# alarm-interface.net
KiCad netlist of a schematic drawn in Altium Designer
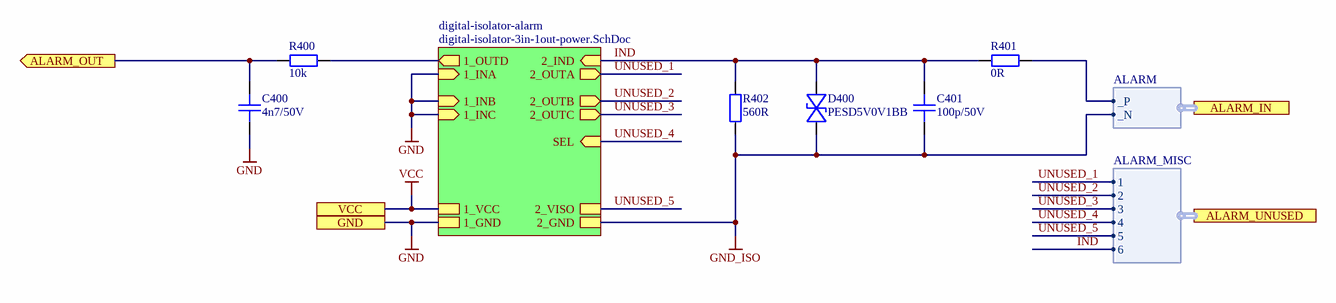
[diagram p0: alarm-interface.SchDoc]

(export (version "E")
  (design (tool "Eeschema 10.0.6"))
  (components
    (comp (ref "C400")
      (value "4n7/50V")
      (footprint "CAPC1608X08N")
      (description "MLCC")
      (fields (field (name "PART NUMBER") "gen_C_ceramic_4n7_50V_X7R_0603"))
      (libsource (lib "OE750") (part "C"))
    )
    (comp (ref "C401")
      (value "100p/50V")
      (footprint "CAPC1608X08N")
      (description "MLCC")
      (fields
        (field (name "PART NUMBER") "gen_C_ceramic_100p_50V_C0G_0603")
        (field (name "TOLERANCE") "± 10%")
      )
      (libsource (lib "OE750") (part "C"))
    )
    (comp (ref "D400")
      (value "PESD5V0V1BB")
      (footprint "SOD523_PESD_NEXPERIA")
      (description "Very low capacitance bidirectional ESD protection diode")
      (fields (field (name "MANUFACTURER") "Nexperia"))
      (libsource (lib "OE750") (part "D_TVS_bi"))
    )
    (comp (ref "R400")
      (value "10k")
      (footprint "RESC1608X05N")
      (description "SMD Resistor 10k 0603")
      (fields (field (name "PART NUMBER") "gen_R_10k_0603") (field (name "TOLERANCE") "1%"))
      (libsource (lib "OE750") (part "R"))
    )
    (comp (ref "R401")
      (value "0R")
      (footprint "RESC1608X05N")
      (description "SMD Resistor 0R 0603")
      (fields (field (name "PART NUMBER") "gen_R_0R_0603") (field (name "POWER") "0.1W"))
      (libsource (lib "OE750") (part "R"))
    )
    (comp (ref "R402")
      (value "560R")
      (footprint "RESC1608X05N")
      (description "SMD Resistor 560R 0603")
      (fields (field (name "PART NUMBER") "gen_R_560R_0603") (field (name "TOLERANCE") "1%"))
      (libsource (lib "OE750") (part "R"))
    )
  )
  (nets
    (net (code "3") (name "/1_OUTD") (class "Default")
      (node (ref "R400") (pin "1") (pinfunction "1_1") (pintype "passive"))
    )
    (net (code "4") (name "/ALARM_OUT") (class "Default")
      (node (ref "C400") (pin "2") (pinfunction "2_2") (pintype "passive"))
      (node (ref "R400") (pin "2") (pinfunction "2_2") (pintype "passive"))
    )
    (net (code "5") (name "/IND") (class "Default")
      (node (ref "C401") (pin "2") (pinfunction "2_2") (pintype "passive"))
      (node (ref "D400") (pin "1") (pinfunction "C_1") (pintype "passive"))
      (node (ref "R401") (pin "1") (pinfunction "1_1") (pintype "passive"))
      (node (ref "R402") (pin "1") (pinfunction "1_1") (pintype "passive"))
    )
    (net (code "11") (name "/_P") (class "Default")
      (node (ref "R401") (pin "2") (pinfunction "2_2") (pintype "passive"))
    )
    (net (code "14") (name "GND") (class "Default")
      (node (ref "C400") (pin "1") (pinfunction "1_1") (pintype "passive"))
    )
    (net (code "15") (name "GND_ISO") (class "Default")
      (node (ref "C401") (pin "1") (pinfunction "1_1") (pintype "passive"))
      (node (ref "D400") (pin "2") (pinfunction "A_2") (pintype "passive"))
      (node (ref "R402") (pin "2") (pinfunction "2_2") (pintype "passive"))
    )
  )
)
